# Striptease-Teensy4_1-v1_2.net
KiCad netlist of a schematic drawn in EAGLE
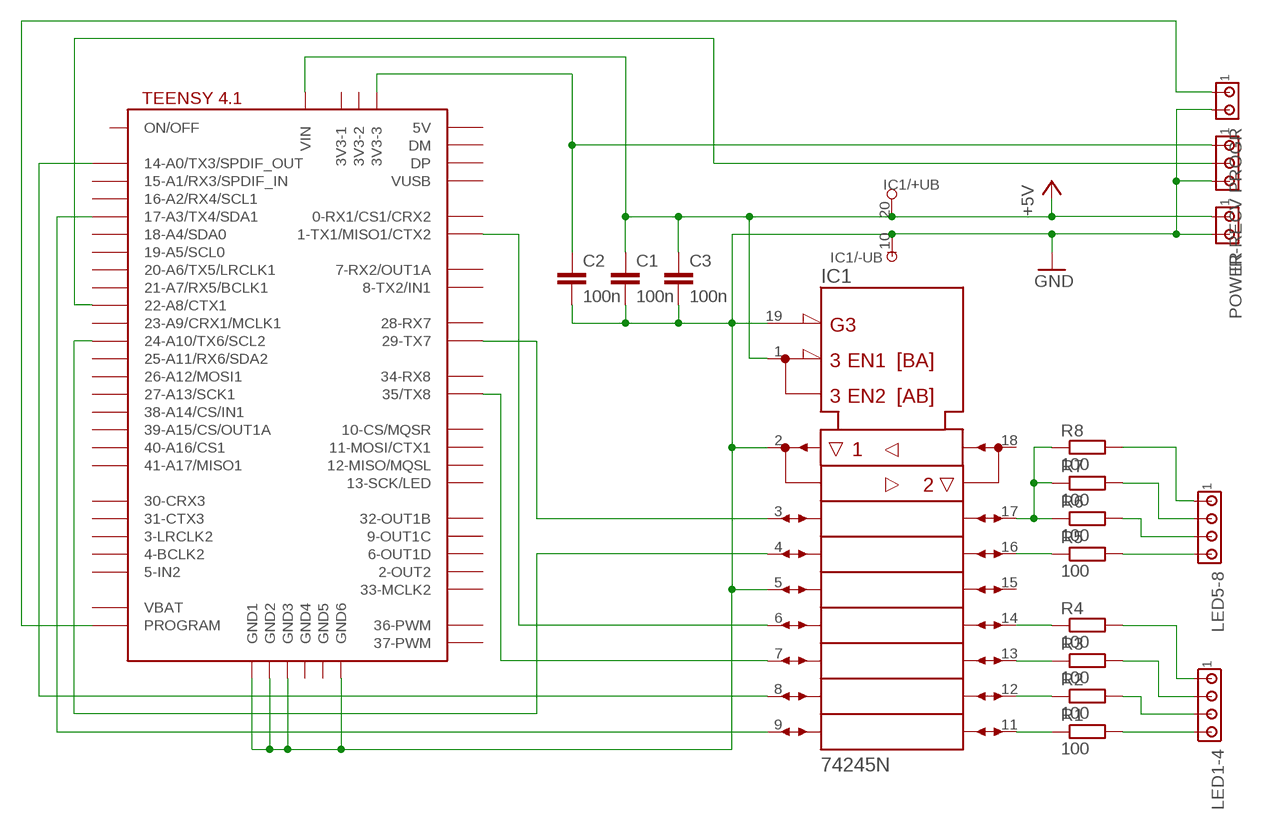
[diagram p0: schematic, sheet 1]

(export (version "E")
  (design (tool "Eeschema 10.0.6"))
  (components
    (comp (ref "C1")
      (value "100n")
      (footprint "eagle-import:C050-025X075")
      (libsource (lib "eagle-import") (part "C-EU050-025X075"))
    )
    (comp (ref "C2")
      (value "100n")
      (footprint "eagle-import:C050-025X075")
      (libsource (lib "eagle-import") (part "C-EU050-025X075"))
    )
    (comp (ref "C3")
      (value "100n")
      (footprint "eagle-import:C050-025X075")
      (libsource (lib "eagle-import") (part "C-EU050-025X075"))
    )
    (comp (ref "IC1")
      (value "74245N")
      (footprint "eagle-import:DIL20")
      (libsource (lib "eagle-import") (part "74245N"))
    )
    (comp (ref "IR-RECV")
      (value "MTA03-100")
      (footprint "eagle-import:10X03MTA")
      (libsource (lib "eagle-import") (part "MTA03-100"))
    )
    (comp (ref "LED1-4")
      (value "MTA04-100")
      (footprint "eagle-import:10X04MTA")
      (libsource (lib "eagle-import") (part "MTA04-100"))
    )
    (comp (ref "LED5-8")
      (value "MTA04-100")
      (footprint "eagle-import:10X04MTA")
      (libsource (lib "eagle-import") (part "MTA04-100"))
    )
    (comp (ref "POWER")
      (value "MTA02-100")
      (footprint "eagle-import:10X02MTA")
      (libsource (lib "eagle-import") (part "MTA02-100"))
    )
    (comp (ref "PROGR")
      (value "MTA02-100")
      (footprint "eagle-import:10X02MTA")
      (libsource (lib "eagle-import") (part "MTA02-100"))
    )
    (comp (ref "R1")
      (value "100")
      (footprint "eagle-import:0207_10")
      (libsource (lib "eagle-import") (part "R-EU_0207/10"))
    )
    (comp (ref "R2")
      (value "100")
      (footprint "eagle-import:0207_10")
      (libsource (lib "eagle-import") (part "R-EU_0207/10"))
    )
    (comp (ref "R3")
      (value "100")
      (footprint "eagle-import:0207_10")
      (libsource (lib "eagle-import") (part "R-EU_0207/10"))
    )
    (comp (ref "R4")
      (value "100")
      (footprint "eagle-import:0207_10")
      (libsource (lib "eagle-import") (part "R-EU_0207/10"))
    )
    (comp (ref "R5")
      (value "100")
      (footprint "eagle-import:0207_10")
      (libsource (lib "eagle-import") (part "R-EU_0207/10"))
    )
    (comp (ref "R6")
      (value "100")
      (footprint "eagle-import:0207_10")
      (libsource (lib "eagle-import") (part "R-EU_0207/10"))
    )
    (comp (ref "R7")
      (value "100")
      (footprint "eagle-import:0207_10")
      (libsource (lib "eagle-import") (part "R-EU_0207/10"))
    )
    (comp (ref "R8")
      (value "100")
      (footprint "eagle-import:0207_10")
      (libsource (lib "eagle-import") (part "R-EU_0207/10"))
    )
    (comp (ref "U$3")
      (value "TEENSY41-E")
      (footprint "eagle-import:TENNSY41-E")
      (libsource (lib "eagle-import") (part "TEENSY41-E"))
    )
  )
  (nets
    (net (code "1") (name "+5V") (class "Default")
      (node (ref "C1") (pin "1") (pinfunction "1_1") (pintype "passive"))
      (node (ref "C3") (pin "1") (pinfunction "1_1") (pintype "passive"))
      (node (ref "IC1") (pin "1") (pinfunction "DIR_1") (pintype "input"))
      (node (ref "IC1") (pin "20") (pinfunction "+UB_20") (pintype "power_in"))
      (node (ref "POWER") (pin "1") (pinfunction "1_1") (pintype "passive"))
      (node (ref "U$3") (pin "VIN") (pinfunction "VIN_VIN") (pintype "bidirectional"))
    )
    (net (code "2") (name "GND") (class "Default")
      (node (ref "C1") (pin "2") (pinfunction "2_2") (pintype "passive"))
      (node (ref "C2") (pin "2") (pinfunction "2_2") (pintype "passive"))
      (node (ref "C3") (pin "2") (pinfunction "2_2") (pintype "passive"))
      (node (ref "IC1") (pin "10") (pinfunction "-UB_10") (pintype "power_in"))
      (node (ref "IC1") (pin "19") (pinfunction "~{G}_19") (pintype "input"))
      (node (ref "IC1") (pin "2") (pinfunction "A1_2") (pintype "bidirectional"))
      (node (ref "IC1") (pin "5") (pinfunction "A4_5") (pintype "bidirectional"))
      (node (ref "IR-RECV") (pin "3") (pinfunction "3_3") (pintype "passive"))
      (node (ref "POWER") (pin "2") (pinfunction "2_2") (pintype "passive"))
      (node (ref "PROGR") (pin "2") (pinfunction "2_2") (pintype "passive"))
      (node (ref "U$3") (pin "GND1") (pinfunction "GND1_GND1") (pintype "bidirectional"))
      (node (ref "U$3") (pin "GND2") (pinfunction "GND2_GND2") (pintype "bidirectional"))
      (node (ref "U$3") (pin "GND3") (pinfunction "GND3_GND3") (pintype "bidirectional"))
      (node (ref "U$3") (pin "GND6") (pinfunction "GND6_GND6") (pintype "bidirectional"))
    )
    (net (code "3") (name "Net-(C2-Pad1)") (class "Default")
      (node (ref "C2") (pin "1") (pinfunction "1_1") (pintype "passive"))
      (node (ref "IR-RECV") (pin "1") (pinfunction "1_1") (pintype "passive"))
      (node (ref "U$3") (pin "3V3-3") (pinfunction "3V3-3_3V3-3") (pintype "bidirectional"))
    )
    (net (code "4") (name "Net-(IC1C-A2)") (class "Default")
      (node (ref "IC1") (pin "3") (pinfunction "A2_3") (pintype "bidirectional"))
      (node (ref "U$3") (pin "29-TX7") (pinfunction "29-TX7_29-TX7") (pintype "bidirectional"))
    )
    (net (code "5") (name "Net-(IC1C-A3)") (class "Default")
      (node (ref "IC1") (pin "4") (pinfunction "A3_4") (pintype "bidirectional"))
      (node (ref "U$3") (pin "24-A10/TX6/SCL2") (pinfunction "24-A10/TX6/SCL2_24-A10/TX6/SCL2") (pintype "bidirectional"))
    )
    (net (code "6") (name "Net-(IC1C-A5)") (class "Default")
      (node (ref "IC1") (pin "6") (pinfunction "A5_6") (pintype "bidirectional"))
      (node (ref "U$3") (pin "1-TX1/MISO1/CTX2") (pinfunction "1-TX1/MISO1/CTX2_1-TX1/MISO1/CTX2") (pintype "bidirectional"))
    )
    (net (code "7") (name "Net-(IC1C-A6)") (class "Default")
      (node (ref "IC1") (pin "7") (pinfunction "A6_7") (pintype "bidirectional"))
      (node (ref "U$3") (pin "35-TX8") (pinfunction "35/TX8_35-TX8") (pintype "bidirectional"))
    )
    (net (code "8") (name "Net-(IC1C-A7)") (class "Default")
      (node (ref "IC1") (pin "8") (pinfunction "A7_8") (pintype "bidirectional"))
      (node (ref "U$3") (pin "14-A0/TX3/SPDIF_OUT") (pinfunction "14-A0/TX3/SPDIF_OUT_14-A0/TX3/SPDIF_OUT") (pintype "bidirectional"))
    )
    (net (code "9") (name "Net-(IC1C-A8)") (class "Default")
      (node (ref "IC1") (pin "9") (pinfunction "A8_9") (pintype "bidirectional"))
      (node (ref "U$3") (pin "17-A3/TX4/SDA1") (pinfunction "17-A3/TX4/SDA1_17-A3/TX4/SDA1") (pintype "bidirectional"))
    )
    (net (code "10") (name "Net-(IC1C-B2)") (class "Default")
      (node (ref "IC1") (pin "17") (pinfunction "B2_17") (pintype "bidirectional"))
      (node (ref "R6") (pin "1") (pinfunction "1_1") (pintype "passive"))
      (node (ref "R7") (pin "1") (pinfunction "1_1") (pintype "passive"))
      (node (ref "R8") (pin "1") (pinfunction "1_1") (pintype "passive"))
    )
    (net (code "11") (name "Net-(IC1C-B3)") (class "Default")
      (node (ref "IC1") (pin "16") (pinfunction "B3_16") (pintype "bidirectional"))
      (node (ref "R5") (pin "1") (pinfunction "1_1") (pintype "passive"))
    )
    (net (code "12") (name "Net-(IC1C-B5)") (class "Default")
      (node (ref "IC1") (pin "14") (pinfunction "B5_14") (pintype "bidirectional"))
      (node (ref "R4") (pin "1") (pinfunction "1_1") (pintype "passive"))
    )
    (net (code "13") (name "Net-(IC1C-B6)") (class "Default")
      (node (ref "IC1") (pin "13") (pinfunction "B6_13") (pintype "bidirectional"))
      (node (ref "R3") (pin "1") (pinfunction "1_1") (pintype "passive"))
    )
    (net (code "14") (name "Net-(IC1C-B7)") (class "Default")
      (node (ref "IC1") (pin "12") (pinfunction "B7_12") (pintype "bidirectional"))
      (node (ref "R2") (pin "1") (pinfunction "1_1") (pintype "passive"))
    )
    (net (code "15") (name "Net-(IC1C-B8)") (class "Default")
      (node (ref "IC1") (pin "11") (pinfunction "B8_11") (pintype "bidirectional"))
      (node (ref "R1") (pin "1") (pinfunction "1_1") (pintype "passive"))
    )
    (net (code "16") (name "Net-(IR-RECV-Pad2)") (class "Default")
      (node (ref "IR-RECV") (pin "2") (pinfunction "2_2") (pintype "passive"))
      (node (ref "U$3") (pin "22-A8/CTX1") (pinfunction "22-A8/CTX1_22-A8/CTX1") (pintype "bidirectional"))
    )
    (net (code "17") (name "Net-(LED1-4-Pad1)") (class "Default")
      (node (ref "LED1-4") (pin "1") (pinfunction "1_1") (pintype "passive"))
      (node (ref "R4") (pin "2") (pinfunction "2_2") (pintype "passive"))
    )
    (net (code "18") (name "Net-(LED1-4-Pad2)") (class "Default")
      (node (ref "LED1-4") (pin "2") (pinfunction "2_2") (pintype "passive"))
      (node (ref "R3") (pin "2") (pinfunction "2_2") (pintype "passive"))
    )
    (net (code "19") (name "Net-(LED1-4-Pad3)") (class "Default")
      (node (ref "LED1-4") (pin "3") (pinfunction "3_3") (pintype "passive"))
      (node (ref "R2") (pin "2") (pinfunction "2_2") (pintype "passive"))
    )
    (net (code "20") (name "Net-(LED1-4-Pad4)") (class "Default")
      (node (ref "LED1-4") (pin "4") (pinfunction "4_4") (pintype "passive"))
      (node (ref "R1") (pin "2") (pinfunction "2_2") (pintype "passive"))
    )
    (net (code "21") (name "Net-(LED5-8-Pad1)") (class "Default")
      (node (ref "LED5-8") (pin "1") (pinfunction "1_1") (pintype "passive"))
      (node (ref "R8") (pin "2") (pinfunction "2_2") (pintype "passive"))
    )
    (net (code "22") (name "Net-(LED5-8-Pad2)") (class "Default")
      (node (ref "LED5-8") (pin "2") (pinfunction "2_2") (pintype "passive"))
      (node (ref "R7") (pin "2") (pinfunction "2_2") (pintype "passive"))
    )
    (net (code "23") (name "Net-(LED5-8-Pad3)") (class "Default")
      (node (ref "LED5-8") (pin "3") (pinfunction "3_3") (pintype "passive"))
      (node (ref "R6") (pin "2") (pinfunction "2_2") (pintype "passive"))
    )
    (net (code "24") (name "Net-(LED5-8-Pad4)") (class "Default")
      (node (ref "LED5-8") (pin "4") (pinfunction "4_4") (pintype "passive"))
      (node (ref "R5") (pin "2") (pinfunction "2_2") (pintype "passive"))
    )
    (net (code "25") (name "Net-(PROGR-Pad1)") (class "Default")
      (node (ref "PROGR") (pin "1") (pinfunction "1_1") (pintype "passive"))
      (node (ref "U$3") (pin "PROGRAM") (pinfunction "PROGRAM_PROGRAM") (pintype "bidirectional"))
    )
    (net (code "26") (name "unconnected-(IC1C-B1-Pad18)") (class "Default")
      (node (ref "IC1") (pin "18") (pinfunction "B1_18") (pintype "bidirectional"))
    )
    (net (code "27") (name "unconnected-(IC1C-B4-Pad15)") (class "Default")
      (node (ref "IC1") (pin "15") (pinfunction "B4_15") (pintype "bidirectional"))
    )
    (net (code "28") (name "unconnected-(U$3-5V-Pad+5V)") (class "Default")
      (node (ref "U$3") (pin "+5V") (pinfunction "5V_+5V") (pintype "bidirectional"))
    )
    (net (code "29") (name "unconnected-(U$3-10-CS{slash}MQSR-Pad10-CS\\MQSR)") (class "Default")
      (node (ref "U$3") (pin "10-CS\\MQSR") (pinfunction "10-CS/MQSR_10-CS\\MQSR") (pintype "bidirectional"))
    )
    (net (code "30") (name "unconnected-(U$3-Pad0-RX1{slash}CS1{slash}CRX2)") (class "Default")
      (node (ref "U$3") (pin "0-RX1/CS1/CRX2") (pinfunction "0-RX1/CS1/CRX2_0-RX1/CS1/CRX2") (pintype "bidirectional"))
    )
    (net (code "31") (name "unconnected-(U$3-Pad2-OUT2)") (class "Default")
      (node (ref "U$3") (pin "2-OUT2") (pinfunction "2-OUT2_2-OUT2") (pintype "bidirectional"))
    )
    (net (code "32") (name "unconnected-(U$3-Pad3-LRCLK2)") (class "Default")
      (node (ref "U$3") (pin "3-LRCLK2") (pinfunction "3-LRCLK2_3-LRCLK2") (pintype "bidirectional"))
    )
    (net (code "33") (name "unconnected-(U$3-Pad3V3-1)") (class "Default")
      (node (ref "U$3") (pin "3V3-1") (pinfunction "3V3-1_3V3-1") (pintype "bidirectional"))
    )
    (net (code "34") (name "unconnected-(U$3-Pad3V3-2)") (class "Default")
      (node (ref "U$3") (pin "3V3-2") (pinfunction "3V3-2_3V3-2") (pintype "bidirectional"))
    )
    (net (code "35") (name "unconnected-(U$3-Pad4-BCLK2)") (class "Default")
      (node (ref "U$3") (pin "4-BCLK2") (pinfunction "4-BCLK2_4-BCLK2") (pintype "bidirectional"))
    )
    (net (code "36") (name "unconnected-(U$3-Pad5-IN2)") (class "Default")
      (node (ref "U$3") (pin "5-IN2") (pinfunction "5-IN2_5-IN2") (pintype "bidirectional"))
    )
    (net (code "37") (name "unconnected-(U$3-Pad6-OUT1D)") (class "Default")
      (node (ref "U$3") (pin "6-OUT1D") (pinfunction "6-OUT1D_6-OUT1D") (pintype "bidirectional"))
    )
    (net (code "38") (name "unconnected-(U$3-Pad7-RX2{slash}OUT1A)") (class "Default")
      (node (ref "U$3") (pin "7-RX2/OUT1A") (pinfunction "7-RX2/OUT1A_7-RX2/OUT1A") (pintype "bidirectional"))
    )
    (net (code "39") (name "unconnected-(U$3-Pad8-TX2{slash}IN1)") (class "Default")
      (node (ref "U$3") (pin "8-TX2/IN1") (pinfunction "8-TX2/IN1_8-TX2/IN1") (pintype "bidirectional"))
    )
    (net (code "40") (name "unconnected-(U$3-Pad9-OUT1C)") (class "Default")
      (node (ref "U$3") (pin "9-OUT1C") (pinfunction "9-OUT1C_9-OUT1C") (pintype "bidirectional"))
    )
    (net (code "41") (name "unconnected-(U$3-Pad11-MOSI{slash}CTX1)") (class "Default")
      (node (ref "U$3") (pin "11-MOSI/CTX1") (pinfunction "11-MOSI/CTX1_11-MOSI/CTX1") (pintype "bidirectional"))
    )
    (net (code "42") (name "unconnected-(U$3-Pad12-MISO{slash}MQSL)") (class "Default")
      (node (ref "U$3") (pin "12-MISO/MQSL") (pinfunction "12-MISO/MQSL_12-MISO/MQSL") (pintype "bidirectional"))
    )
    (net (code "43") (name "unconnected-(U$3-Pad13-SCK{slash}LED)") (class "Default")
      (node (ref "U$3") (pin "13-SCK/LED") (pinfunction "13-SCK/LED_13-SCK/LED") (pintype "bidirectional"))
    )
    (net (code "44") (name "unconnected-(U$3-Pad15-A1{slash}RX3{slash}SPDIF_IN)") (class "Default")
      (node (ref "U$3") (pin "15-A1/RX3/SPDIF_IN") (pinfunction "15-A1/RX3/SPDIF_IN_15-A1/RX3/SPDIF_IN") (pintype "bidirectional"))
    )
    (net (code "45") (name "unconnected-(U$3-Pad16-A2{slash}RX4{slash}SCL1)") (class "Default")
      (node (ref "U$3") (pin "16-A2/RX4/SCL1") (pinfunction "16-A2/RX4/SCL1_16-A2/RX4/SCL1") (pintype "bidirectional"))
    )
    (net (code "46") (name "unconnected-(U$3-Pad18-A4{slash}SDA0)") (class "Default")
      (node (ref "U$3") (pin "18-A4/SDA0") (pinfunction "18-A4/SDA0_18-A4/SDA0") (pintype "bidirectional"))
    )
    (net (code "47") (name "unconnected-(U$3-Pad19-A5{slash}SCL0)") (class "Default")
      (node (ref "U$3") (pin "19-A5/SCL0") (pinfunction "19-A5/SCL0_19-A5/SCL0") (pintype "bidirectional"))
    )
    (net (code "48") (name "unconnected-(U$3-Pad20-A6{slash}TX5{slash}LRCLK1)") (class "Default")
      (node (ref "U$3") (pin "20-A6/TX5/LRCLK1") (pinfunction "20-A6/TX5/LRCLK1_20-A6/TX5/LRCLK1") (pintype "bidirectional"))
    )
    (net (code "49") (name "unconnected-(U$3-Pad21-A7{slash}RX5{slash}BCLK1)") (class "Default")
      (node (ref "U$3") (pin "21-A7/RX5/BCLK1") (pinfunction "21-A7/RX5/BCLK1_21-A7/RX5/BCLK1") (pintype "bidirectional"))
    )
    (net (code "50") (name "unconnected-(U$3-Pad23-A9{slash}CRX1{slash}MCLK1)") (class "Default")
      (node (ref "U$3") (pin "23-A9/CRX1/MCLK1") (pinfunction "23-A9/CRX1/MCLK1_23-A9/CRX1/MCLK1") (pintype "bidirectional"))
    )
    (net (code "51") (name "unconnected-(U$3-Pad25-A11{slash}RX6{slash}SDA2)") (class "Default")
      (node (ref "U$3") (pin "25-A11/RX6/SDA2") (pinfunction "25-A11/RX6/SDA2_25-A11/RX6/SDA2") (pintype "bidirectional"))
    )
    (net (code "52") (name "unconnected-(U$3-Pad26-A12{slash}MOSI1)") (class "Default")
      (node (ref "U$3") (pin "26-A12/MOSI1") (pinfunction "26-A12/MOSI1_26-A12/MOSI1") (pintype "bidirectional"))
    )
    (net (code "53") (name "unconnected-(U$3-Pad27-A13{slash}SCK1)") (class "Default")
      (node (ref "U$3") (pin "27-A13/SCK1") (pinfunction "27-A13/SCK1_27-A13/SCK1") (pintype "bidirectional"))
    )
    (net (code "54") (name "unconnected-(U$3-Pad28-RX7)") (class "Default")
      (node (ref "U$3") (pin "28-RX7") (pinfunction "28-RX7_28-RX7") (pintype "bidirectional"))
    )
    (net (code "55") (name "unconnected-(U$3-Pad30-CRX3)") (class "Default")
      (node (ref "U$3") (pin "30-CRX3") (pinfunction "30-CRX3_30-CRX3") (pintype "bidirectional"))
    )
    (net (code "56") (name "unconnected-(U$3-Pad31-CTX3)") (class "Default")
      (node (ref "U$3") (pin "31-CTX3") (pinfunction "31-CTX3_31-CTX3") (pintype "bidirectional"))
    )
    (net (code "57") (name "unconnected-(U$3-Pad32-OUT1B)") (class "Default")
      (node (ref "U$3") (pin "32-OUT1B") (pinfunction "32-OUT1B_32-OUT1B") (pintype "bidirectional"))
    )
    (net (code "58") (name "unconnected-(U$3-Pad33-MCLK2)") (class "Default")
      (node (ref "U$3") (pin "33-MCLK2") (pinfunction "33-MCLK2_33-MCLK2") (pintype "bidirectional"))
    )
    (net (code "59") (name "unconnected-(U$3-Pad34-RX8)") (class "Default")
      (node (ref "U$3") (pin "34-RX8") (pinfunction "34-RX8_34-RX8") (pintype "bidirectional"))
    )
    (net (code "60") (name "unconnected-(U$3-Pad36-PWM)") (class "Default")
      (node (ref "U$3") (pin "36-PWM") (pinfunction "36-PWM_36-PWM") (pintype "bidirectional"))
    )
    (net (code "61") (name "unconnected-(U$3-Pad37-PWM)") (class "Default")
      (node (ref "U$3") (pin "37-PWM") (pinfunction "37-PWM_37-PWM") (pintype "bidirectional"))
    )
    (net (code "62") (name "unconnected-(U$3-Pad38-A14{slash}CS{slash}IN1)") (class "Default")
      (node (ref "U$3") (pin "38-A14/CS/IN1") (pinfunction "38-A14/CS/IN1_38-A14/CS/IN1") (pintype "bidirectional"))
    )
    (net (code "63") (name "unconnected-(U$3-Pad39-A15{slash}CS{slash}OUT1A)") (class "Default")
      (node (ref "U$3") (pin "39-A15/CS/OUT1A") (pinfunction "39-A15/CS/OUT1A_39-A15/CS/OUT1A") (pintype "bidirectional"))
    )
    (net (code "64") (name "unconnected-(U$3-Pad40-A16{slash}CS1)") (class "Default")
      (node (ref "U$3") (pin "40-A16/CS1") (pinfunction "40-A16/CS1_40-A16/CS1") (pintype "bidirectional"))
    )
    (net (code "65") (name "unconnected-(U$3-Pad41-A17{slash}MISO1)") (class "Default")
      (node (ref "U$3") (pin "41-A17/MISO1") (pinfunction "41-A17/MISO1_41-A17/MISO1") (pintype "bidirectional"))
    )
    (net (code "66") (name "unconnected-(U$3-PadDM)") (class "Default")
      (node (ref "U$3") (pin "DM") (pinfunction "DM_DM") (pintype "bidirectional"))
    )
    (net (code "67") (name "unconnected-(U$3-PadDP)") (class "Default")
      (node (ref "U$3") (pin "DP") (pinfunction "DP_DP") (pintype "bidirectional"))
    )
    (net (code "68") (name "unconnected-(U$3-PadGND4)") (class "Default")
      (node (ref "U$3") (pin "GND4") (pinfunction "GND4_GND4") (pintype "bidirectional"))
    )
    (net (code "69") (name "unconnected-(U$3-PadGND5)") (class "Default")
      (node (ref "U$3") (pin "GND5") (pinfunction "GND5_GND5") (pintype "bidirectional"))
    )
    (net (code "70") (name "unconnected-(U$3-PadON{slash}OFF)") (class "Default")
      (node (ref "U$3") (pin "ON/OFF") (pinfunction "ON/OFF_ON/OFF") (pintype "bidirectional"))
    )
    (net (code "71") (name "unconnected-(U$3-PadVBAT)") (class "Default")
      (node (ref "U$3") (pin "VBAT") (pinfunction "VBAT_VBAT") (pintype "bidirectional"))
    )
    (net (code "72") (name "unconnected-(U$3-PadVUSB)") (class "Default")
      (node (ref "U$3") (pin "VUSB") (pinfunction "VUSB_VUSB") (pintype "bidirectional"))
    )
  )
)
